# USB-to-UART.net
KiCad netlist of a schematic drawn in EAGLE
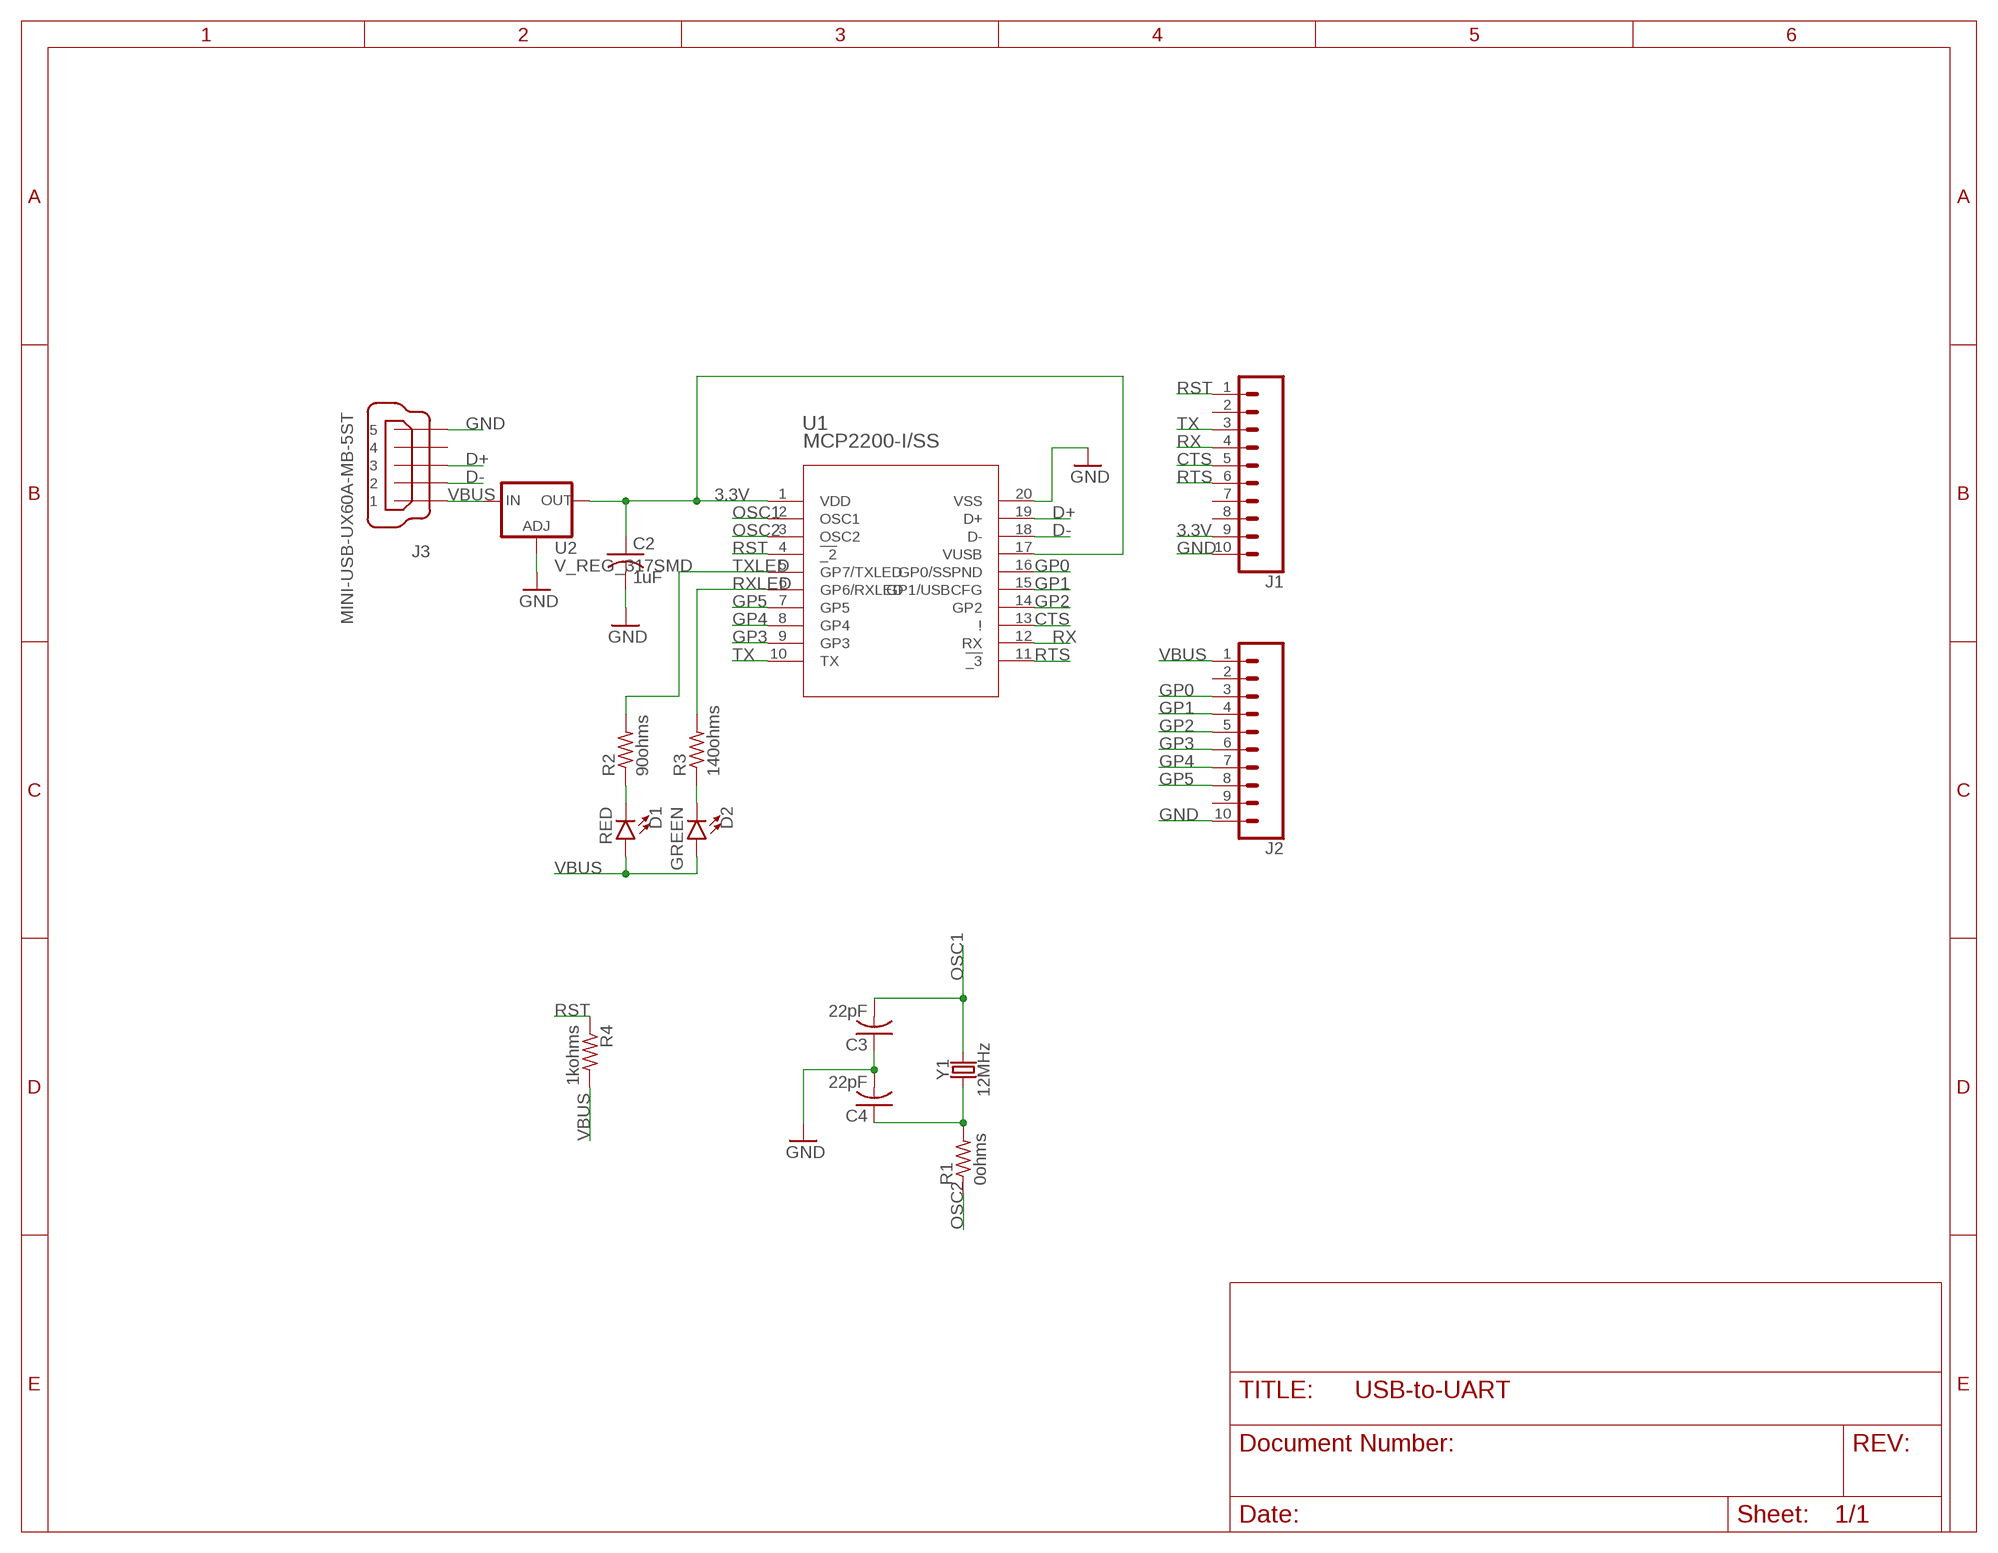
[diagram p0: schematic, sheet 1]

(export (version "E")
  (design (tool "Eeschema 10.0.6"))
  (components
    (comp (ref "C2")
      (value "1uF")
      (footprint "eagle-import:C0603")
      (libsource (lib "eagle-import") (part "C-USC0603"))
    )
    (comp (ref "C3")
      (value "22pF")
      (footprint "eagle-import:C0603")
      (libsource (lib "eagle-import") (part "C-USC0603"))
    )
    (comp (ref "C4")
      (value "22pF")
      (footprint "eagle-import:C0603")
      (libsource (lib "eagle-import") (part "C-USC0603"))
    )
    (comp (ref "D1")
      (value "RED")
      (footprint "eagle-import:LED-0603")
      (libsource (lib "eagle-import") (part "LED0603"))
    )
    (comp (ref "D2")
      (value "GREEN")
      (footprint "eagle-import:LED-0603")
      (libsource (lib "eagle-import") (part "LED0603"))
    )
    (comp (ref "J1")
      (value "CONN_10\"")
      (footprint "eagle-import:1X10")
      (libsource (lib "eagle-import") (part "CONN_10{dblquote}"))
    )
    (comp (ref "J2")
      (value "CONN_10\"")
      (footprint "eagle-import:1X10")
      (libsource (lib "eagle-import") (part "CONN_10{dblquote}"))
    )
    (comp (ref "J3")
      (value "MINI-USB-UX60A-MB-5ST")
      (footprint "eagle-import:UX60A-MB-5ST")
      (libsource (lib "eagle-import") (part "MINI-USB-UX60A-MB-5ST"))
    )
    (comp (ref "R1")
      (value "0ohms")
      (footprint "eagle-import:R0603")
      (libsource (lib "eagle-import") (part "R-US_R0603"))
    )
    (comp (ref "R2")
      (value "90ohms")
      (footprint "eagle-import:R0603")
      (libsource (lib "eagle-import") (part "R-US_R0603"))
    )
    (comp (ref "R3")
      (value "140ohms")
      (footprint "eagle-import:R0603")
      (libsource (lib "eagle-import") (part "R-US_R0603"))
    )
    (comp (ref "R4")
      (value "1kohms")
      (footprint "eagle-import:R0603")
      (libsource (lib "eagle-import") (part "R-US_R0603"))
    )
    (comp (ref "U1")
      (value "MCP2200-I/SS")
      (footprint "eagle-import:SSOP20_MC")
      (fields (field (name "MANUFACTURER_PART_NUMBER") "MCP2200ISS"))
      (libsource (lib "eagle-import") (part "MCP2200-I/SS"))
    )
    (comp (ref "U2")
      (value "V_REG_317SMD")
      (footprint "eagle-import:SOT223")
      (libsource (lib "eagle-import") (part "V_REG_317SMD"))
    )
    (comp (ref "Y1")
      (value "12MHz")
      (footprint "eagle-import:CRYSTAL-SMD-5X3.2-4PAD")
      (libsource (lib "eagle-import") (part "CRYSTAL-12MHZ{dblquote}"))
    )
  )
  (nets
    (net (code "1") (name "/3.3V") (class "Default")
      (node (ref "C2") (pin "1") (pinfunction "1_1") (pintype "passive"))
      (node (ref "J1") (pin "9") (pinfunction "9_9") (pintype "passive"))
      (node (ref "U1") (pin "1") (pinfunction "VDD_1") (pintype "power_in"))
      (node (ref "U1") (pin "17") (pinfunction "VUSB_17") (pintype "power_in"))
      (node (ref "U2") (pin "2") (pinfunction "OUT_2") (pintype "output"))
    )
    (net (code "2") (name "/CTS") (class "Default")
      (node (ref "J1") (pin "5") (pinfunction "5_5") (pintype "passive"))
      (node (ref "U1") (pin "13") (pinfunction "~_13") (pintype "input"))
    )
    (net (code "3") (name "/D+") (class "Default")
      (node (ref "J3") (pin "3") (pinfunction "3_3") (pintype "input"))
      (node (ref "U1") (pin "19") (pinfunction "D+_19") (pintype "bidirectional"))
    )
    (net (code "4") (name "/D-") (class "Default")
      (node (ref "J3") (pin "2") (pinfunction "2_2") (pintype "input"))
      (node (ref "U1") (pin "18") (pinfunction "D-_18") (pintype "bidirectional"))
    )
    (net (code "5") (name "/GP0") (class "Default")
      (node (ref "J2") (pin "3") (pinfunction "3_3") (pintype "passive"))
      (node (ref "U1") (pin "16") (pinfunction "GP0/SSPND_16") (pintype "bidirectional"))
    )
    (net (code "6") (name "/GP1") (class "Default")
      (node (ref "J2") (pin "4") (pinfunction "4_4") (pintype "passive"))
      (node (ref "U1") (pin "15") (pinfunction "GP1/USBCFG_15") (pintype "bidirectional"))
    )
    (net (code "7") (name "/GP2") (class "Default")
      (node (ref "J2") (pin "5") (pinfunction "5_5") (pintype "passive"))
      (node (ref "U1") (pin "14") (pinfunction "GP2_14") (pintype "bidirectional"))
    )
    (net (code "8") (name "/GP3") (class "Default")
      (node (ref "J2") (pin "6") (pinfunction "6_6") (pintype "passive"))
      (node (ref "U1") (pin "9") (pinfunction "GP3_9") (pintype "bidirectional"))
    )
    (net (code "9") (name "/GP4") (class "Default")
      (node (ref "J2") (pin "7") (pinfunction "7_7") (pintype "passive"))
      (node (ref "U1") (pin "8") (pinfunction "GP4_8") (pintype "bidirectional"))
    )
    (net (code "10") (name "/GP5") (class "Default")
      (node (ref "J2") (pin "8") (pinfunction "8_8") (pintype "passive"))
      (node (ref "U1") (pin "7") (pinfunction "GP5_7") (pintype "bidirectional"))
    )
    (net (code "11") (name "/OSC1") (class "Default")
      (node (ref "C3") (pin "2") (pinfunction "2_2") (pintype "passive"))
      (node (ref "U1") (pin "2") (pinfunction "OSC1_2") (pintype "input"))
      (node (ref "Y1") (pin "3") (pinfunction "2_3") (pintype "passive"))
    )
    (net (code "12") (name "/OSC2") (class "Default")
      (node (ref "R1") (pin "1") (pinfunction "1_1") (pintype "passive"))
      (node (ref "U1") (pin "3") (pinfunction "OSC2_3") (pintype "output"))
    )
    (net (code "13") (name "/RST") (class "Default")
      (node (ref "J1") (pin "1") (pinfunction "1_1") (pintype "passive"))
      (node (ref "R4") (pin "1") (pinfunction "1_1") (pintype "passive"))
      (node (ref "U1") (pin "4") (pinfunction "~{_2}_4") (pintype "input"))
    )
    (net (code "14") (name "/RTS") (class "Default")
      (node (ref "J1") (pin "6") (pinfunction "6_6") (pintype "passive"))
      (node (ref "U1") (pin "11") (pinfunction "~{_3}_11") (pintype "output"))
    )
    (net (code "15") (name "/RX") (class "Default")
      (node (ref "J1") (pin "4") (pinfunction "4_4") (pintype "passive"))
      (node (ref "U1") (pin "12") (pinfunction "RX_12") (pintype "input"))
    )
    (net (code "16") (name "/RXLED") (class "Default")
      (node (ref "R3") (pin "2") (pinfunction "2_2") (pintype "passive"))
      (node (ref "U1") (pin "6") (pinfunction "GP6/RXLED_6") (pintype "bidirectional"))
    )
    (net (code "17") (name "/TX") (class "Default")
      (node (ref "J1") (pin "3") (pinfunction "3_3") (pintype "passive"))
      (node (ref "U1") (pin "10") (pinfunction "TX_10") (pintype "output"))
    )
    (net (code "18") (name "/TXLED") (class "Default")
      (node (ref "R2") (pin "2") (pinfunction "2_2") (pintype "passive"))
      (node (ref "U1") (pin "5") (pinfunction "GP7/TXLED_5") (pintype "bidirectional"))
    )
    (net (code "19") (name "/VBUS") (class "Default")
      (node (ref "D1") (pin "A") (pinfunction "A_A") (pintype "passive"))
      (node (ref "D2") (pin "A") (pinfunction "A_A") (pintype "passive"))
      (node (ref "J2") (pin "1") (pinfunction "1_1") (pintype "passive"))
      (node (ref "J3") (pin "1") (pinfunction "1_1") (pintype "input"))
      (node (ref "R4") (pin "2") (pinfunction "2_2") (pintype "passive"))
      (node (ref "U2") (pin "3") (pinfunction "IN_3") (pintype "input"))
    )
    (net (code "20") (name "GND") (class "Default")
      (node (ref "C2") (pin "2") (pinfunction "2_2") (pintype "passive"))
      (node (ref "C3") (pin "1") (pinfunction "1_1") (pintype "passive"))
      (node (ref "C4") (pin "2") (pinfunction "2_2") (pintype "passive"))
      (node (ref "J1") (pin "10") (pinfunction "10_10") (pintype "passive"))
      (node (ref "J2") (pin "10") (pinfunction "10_10") (pintype "passive"))
      (node (ref "J3") (pin "5") (pinfunction "5_5") (pintype "input"))
      (node (ref "U1") (pin "20") (pinfunction "VSS_20") (pintype "power_in"))
      (node (ref "U2") (pin "1") (pinfunction "ADJ_1") (pintype "input"))
    )
    (net (code "21") (name "Net-(C4-Pad1)") (class "Default")
      (node (ref "C4") (pin "1") (pinfunction "1_1") (pintype "passive"))
      (node (ref "R1") (pin "2") (pinfunction "2_2") (pintype "passive"))
      (node (ref "Y1") (pin "1") (pinfunction "1_1") (pintype "passive"))
    )
    (net (code "22") (name "Net-(D1-PadC)") (class "Default")
      (node (ref "D1") (pin "C") (pinfunction "C_C") (pintype "passive"))
      (node (ref "R2") (pin "1") (pinfunction "1_1") (pintype "passive"))
    )
    (net (code "23") (name "Net-(D2-PadC)") (class "Default")
      (node (ref "D2") (pin "C") (pinfunction "C_C") (pintype "passive"))
      (node (ref "R3") (pin "1") (pinfunction "1_1") (pintype "passive"))
    )
    (net (code "24") (name "unconnected-(J1-Pad2)") (class "Default")
      (node (ref "J1") (pin "2") (pinfunction "2_2") (pintype "passive"))
    )
    (net (code "25") (name "unconnected-(J1-Pad7)") (class "Default")
      (node (ref "J1") (pin "7") (pinfunction "7_7") (pintype "passive"))
    )
    (net (code "26") (name "unconnected-(J1-Pad8)") (class "Default")
      (node (ref "J1") (pin "8") (pinfunction "8_8") (pintype "passive"))
    )
    (net (code "27") (name "unconnected-(J2-Pad2)") (class "Default")
      (node (ref "J2") (pin "2") (pinfunction "2_2") (pintype "passive"))
    )
    (net (code "28") (name "unconnected-(J2-Pad9)") (class "Default")
      (node (ref "J2") (pin "9") (pinfunction "9_9") (pintype "passive"))
    )
    (net (code "29") (name "unconnected-(J3-Pad4)") (class "Default")
      (node (ref "J3") (pin "4") (pinfunction "4_4") (pintype "input"))
    )
  )
)
